# max_plate.net
KiCad netlist of a schematic drawn in EAGLE
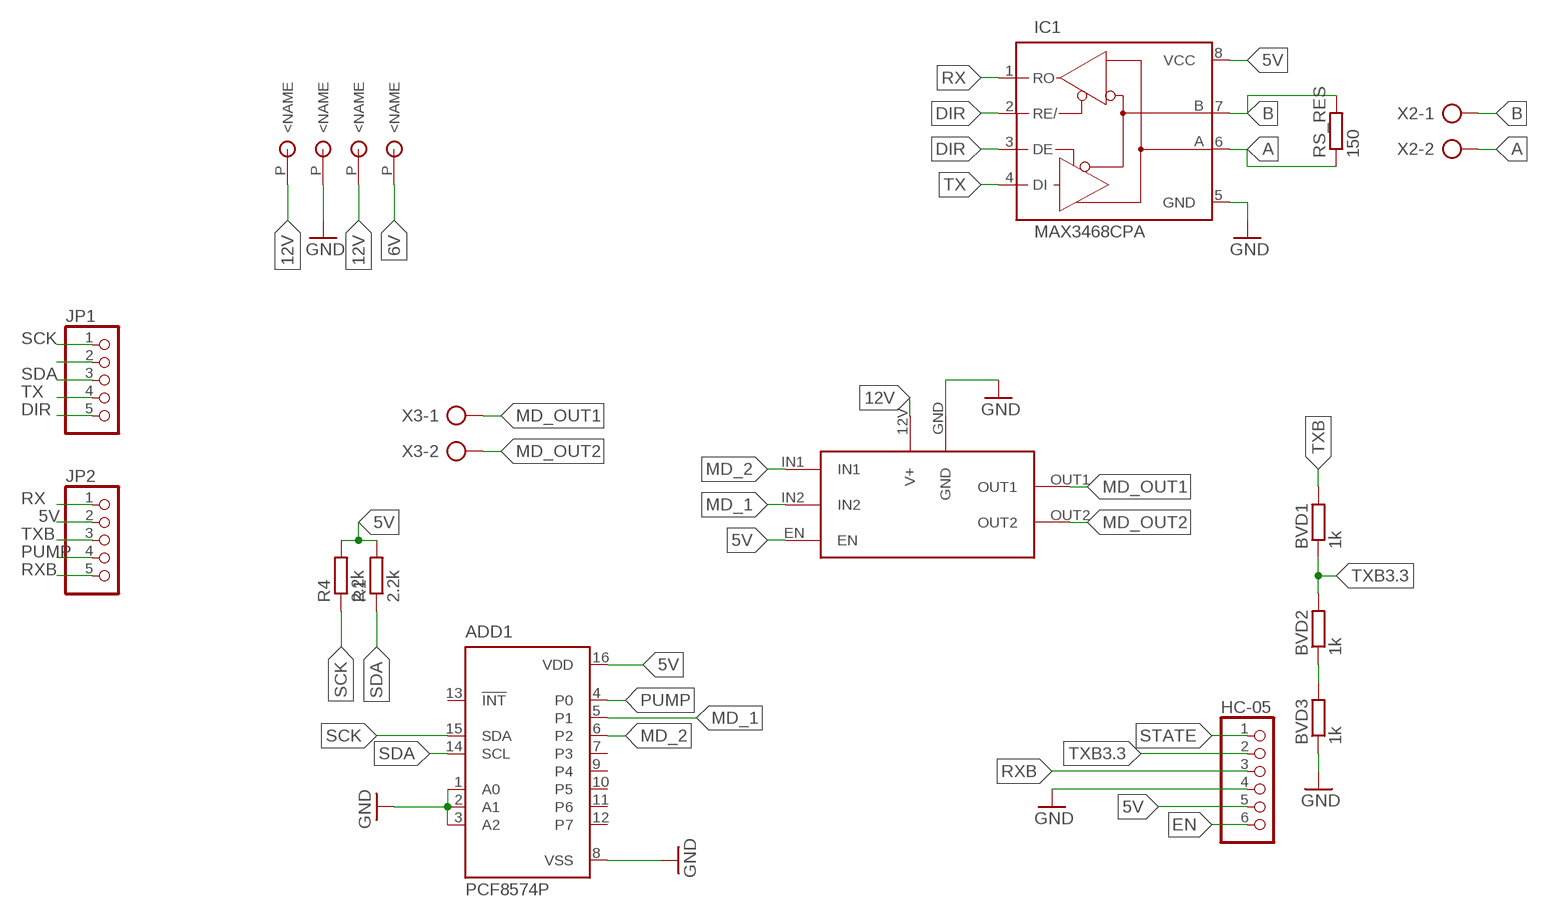
[diagram p0: schematic, sheet 1]

(export (version "E")
  (design (tool "Eeschema 10.0.6"))
  (components
    (comp (ref "ADD1")
      (value "PCF8574P")
      (footprint "eagle-import:DIL16")
      (fields (field (name "MPN") "PCF8574PN"))
      (libsource (lib "eagle-import") (part "PCF8574P"))
    )
    (comp (ref "BVD1")
      (value "1k")
      (footprint "eagle-import:0207_10")
      (libsource (lib "eagle-import") (part "R-EU_0207/10"))
    )
    (comp (ref "BVD2")
      (value "1k")
      (footprint "eagle-import:0207_10")
      (libsource (lib "eagle-import") (part "R-EU_0207/10"))
    )
    (comp (ref "BVD3")
      (value "1k")
      (footprint "eagle-import:0207_10")
      (libsource (lib "eagle-import") (part "R-EU_0207/10"))
    )
    (comp (ref "HC-05")
      (value "PINHD-1X6")
      (footprint "eagle-import:1X06")
      (libsource (lib "eagle-import") (part "PINHD-1X6"))
    )
    (comp (ref "IC1")
      (value "MAX3468CPA")
      (footprint "eagle-import:DIL08")
      (libsource (lib "eagle-import") (part "MAX34PA68C"))
    )
    (comp (ref "JP1")
      (value "PINHD-1X5")
      (footprint "eagle-import:1X05")
      (libsource (lib "eagle-import") (part "PINHD-1X5"))
    )
    (comp (ref "JP2")
      (value "PINHD-1X5")
      (footprint "eagle-import:1X05")
      (libsource (lib "eagle-import") (part "PINHD-1X5"))
    )
    (comp (ref "R1")
      (value "2.2k")
      (footprint "eagle-import:0207_10")
      (libsource (lib "eagle-import") (part "R-EU_0207/10"))
    )
    (comp (ref "R4")
      (value "2.2k")
      (footprint "eagle-import:0207_10")
      (libsource (lib "eagle-import") (part "R-EU_0207/10"))
    )
    (comp (ref "RS_RES")
      (value "150")
      (footprint "eagle-import:0207_10")
      (libsource (lib "eagle-import") (part "R-EU_0207/10"))
    )
    (comp (ref "U$1")
      (value "CU-SPACER")
      (footprint "eagle-import:CU-SPACER")
      (libsource (lib "eagle-import") (part "CU-SPACER"))
    )
    (comp (ref "U$2")
      (value "CU-SPACER")
      (footprint "eagle-import:CU-SPACER")
      (libsource (lib "eagle-import") (part "CU-SPACER"))
    )
    (comp (ref "U$3")
      (value "CU-SPACER")
      (footprint "eagle-import:CU-SPACER")
      (libsource (lib "eagle-import") (part "CU-SPACER"))
    )
    (comp (ref "U$4")
      (value "CU-SPACER")
      (footprint "eagle-import:CU-SPACER")
      (libsource (lib "eagle-import") (part "CU-SPACER"))
    )
    (comp (ref "U$5")
      (value "L6203-MODULE")
      (footprint "eagle-import:L6203-MODULE")
      (libsource (lib "eagle-import") (part "L6203-MODULE"))
    )
    (comp (ref "X2")
      (value "AK500/2")
      (footprint "eagle-import:AK500_2")
      (libsource (lib "eagle-import") (part "AK500/2"))
    )
    (comp (ref "X3")
      (value "AK500/2")
      (footprint "eagle-import:AK500_2")
      (libsource (lib "eagle-import") (part "AK500/2"))
    )
  )
  (nets
    (net (code "1") (name "5V") (class "Default")
      (node (ref "ADD1") (pin "16") (pinfunction "VDD_16") (pintype "power_in"))
      (node (ref "HC-05") (pin "5") (pinfunction "5_5") (pintype "passive"))
      (node (ref "IC1") (pin "8") (pinfunction "VCC_8") (pintype "power_in"))
      (node (ref "JP2") (pin "2") (pinfunction "2_2") (pintype "passive"))
      (node (ref "R1") (pin "2") (pinfunction "2_2") (pintype "passive"))
      (node (ref "R4") (pin "2") (pinfunction "2_2") (pintype "passive"))
      (node (ref "U$5") (pin "EN") (pinfunction "EN_EN") (pintype "bidirectional"))
    )
    (net (code "2") (name "6V") (class "Default")
      (node (ref "U$4") (pin "P") (pinfunction "<NAME_P") (pintype "bidirectional"))
    )
    (net (code "3") (name "12V") (class "Default")
      (node (ref "U$1") (pin "P") (pinfunction "<NAME_P") (pintype "bidirectional"))
      (node (ref "U$3") (pin "P") (pinfunction "<NAME_P") (pintype "bidirectional"))
      (node (ref "U$5") (pin "12V") (pinfunction "V+_12V") (pintype "bidirectional"))
    )
    (net (code "4") (name "A") (class "Default")
      (node (ref "IC1") (pin "6") (pinfunction "A_6") (pintype "passive"))
      (node (ref "RS_RES") (pin "1") (pinfunction "1_1") (pintype "passive"))
      (node (ref "X2") (pin "2") (pinfunction "KL_2") (pintype "passive"))
    )
    (net (code "5") (name "B") (class "Default")
      (node (ref "IC1") (pin "7") (pinfunction "B_7") (pintype "passive"))
      (node (ref "RS_RES") (pin "2") (pinfunction "2_2") (pintype "passive"))
      (node (ref "X2") (pin "1") (pinfunction "KL_1") (pintype "passive"))
    )
    (net (code "6") (name "DIR") (class "Default")
      (node (ref "IC1") (pin "2") (pinfunction "RE/_2") (pintype "input"))
      (node (ref "IC1") (pin "3") (pinfunction "DE_3") (pintype "input"))
      (node (ref "JP1") (pin "5") (pinfunction "5_5") (pintype "passive"))
    )
    (net (code "7") (name "EN") (class "Default")
      (node (ref "HC-05") (pin "6") (pinfunction "6_6") (pintype "passive"))
    )
    (net (code "8") (name "GND") (class "Default")
      (node (ref "ADD1") (pin "1") (pinfunction "A0_1") (pintype "input"))
      (node (ref "ADD1") (pin "2") (pinfunction "A1_2") (pintype "input"))
      (node (ref "ADD1") (pin "3") (pinfunction "A2_3") (pintype "input"))
      (node (ref "ADD1") (pin "8") (pinfunction "VSS_8") (pintype "power_in"))
      (node (ref "BVD3") (pin "1") (pinfunction "1_1") (pintype "passive"))
      (node (ref "HC-05") (pin "4") (pinfunction "4_4") (pintype "passive"))
      (node (ref "IC1") (pin "5") (pinfunction "GND_5") (pintype "power_in"))
      (node (ref "U$2") (pin "P") (pinfunction "<NAME_P") (pintype "bidirectional"))
      (node (ref "U$5") (pin "GND") (pinfunction "GND_GND") (pintype "bidirectional"))
    )
    (net (code "9") (name "MD_1") (class "Default")
      (node (ref "ADD1") (pin "5") (pinfunction "P1_5") (pintype "bidirectional"))
      (node (ref "U$5") (pin "IN2") (pinfunction "IN2_IN2") (pintype "bidirectional"))
    )
    (net (code "10") (name "MD_2") (class "Default")
      (node (ref "ADD1") (pin "6") (pinfunction "P2_6") (pintype "bidirectional"))
      (node (ref "U$5") (pin "IN1") (pinfunction "IN1_IN1") (pintype "bidirectional"))
    )
    (net (code "11") (name "MD_OUT1") (class "Default")
      (node (ref "U$5") (pin "OUT1") (pinfunction "OUT1_OUT1") (pintype "bidirectional"))
      (node (ref "X3") (pin "1") (pinfunction "KL_1") (pintype "passive"))
    )
    (net (code "12") (name "MD_OUT2") (class "Default")
      (node (ref "U$5") (pin "OUT2") (pinfunction "OUT2_OUT2") (pintype "bidirectional"))
      (node (ref "X3") (pin "2") (pinfunction "KL_2") (pintype "passive"))
    )
    (net (code "13") (name "Net-(BVD2-Pad1)") (class "Default")
      (node (ref "BVD2") (pin "1") (pinfunction "1_1") (pintype "passive"))
      (node (ref "BVD3") (pin "2") (pinfunction "2_2") (pintype "passive"))
    )
    (net (code "14") (name "PUMP") (class "Default")
      (node (ref "ADD1") (pin "4") (pinfunction "P0_4") (pintype "bidirectional"))
      (node (ref "JP2") (pin "4") (pinfunction "4_4") (pintype "passive"))
    )
    (net (code "15") (name "RX") (class "Default")
      (node (ref "IC1") (pin "1") (pinfunction "RO_1") (pintype "output"))
      (node (ref "JP2") (pin "1") (pinfunction "1_1") (pintype "passive"))
    )
    (net (code "16") (name "RXB") (class "Default")
      (node (ref "HC-05") (pin "3") (pinfunction "3_3") (pintype "passive"))
      (node (ref "JP2") (pin "5") (pinfunction "5_5") (pintype "passive"))
    )
    (net (code "17") (name "SCK") (class "Default")
      (node (ref "ADD1") (pin "15") (pinfunction "SDA_15") (pintype "bidirectional"))
      (node (ref "JP1") (pin "1") (pinfunction "1_1") (pintype "passive"))
      (node (ref "R4") (pin "1") (pinfunction "1_1") (pintype "passive"))
    )
    (net (code "18") (name "SDA") (class "Default")
      (node (ref "ADD1") (pin "14") (pinfunction "SCL_14") (pintype "input"))
      (node (ref "JP1") (pin "3") (pinfunction "3_3") (pintype "passive"))
      (node (ref "R1") (pin "1") (pinfunction "1_1") (pintype "passive"))
    )
    (net (code "19") (name "STATE") (class "Default")
      (node (ref "HC-05") (pin "1") (pinfunction "1_1") (pintype "passive"))
    )
    (net (code "20") (name "TX") (class "Default")
      (node (ref "IC1") (pin "4") (pinfunction "DI_4") (pintype "input"))
      (node (ref "JP1") (pin "4") (pinfunction "4_4") (pintype "passive"))
    )
    (net (code "21") (name "TXB") (class "Default")
      (node (ref "BVD1") (pin "2") (pinfunction "2_2") (pintype "passive"))
      (node (ref "JP2") (pin "3") (pinfunction "3_3") (pintype "passive"))
    )
    (net (code "22") (name "TXB3.3") (class "Default")
      (node (ref "BVD1") (pin "1") (pinfunction "1_1") (pintype "passive"))
      (node (ref "BVD2") (pin "2") (pinfunction "2_2") (pintype "passive"))
      (node (ref "HC-05") (pin "2") (pinfunction "2_2") (pintype "passive"))
    )
    (net (code "23") (name "unconnected-(ADD1-P3-Pad7)") (class "Default")
      (node (ref "ADD1") (pin "7") (pinfunction "P3_7") (pintype "bidirectional"))
    )
    (net (code "24") (name "unconnected-(ADD1-P4-Pad9)") (class "Default")
      (node (ref "ADD1") (pin "9") (pinfunction "P4_9") (pintype "bidirectional"))
    )
    (net (code "25") (name "unconnected-(ADD1-P5-Pad10)") (class "Default")
      (node (ref "ADD1") (pin "10") (pinfunction "P5_10") (pintype "bidirectional"))
    )
    (net (code "26") (name "unconnected-(ADD1-P6-Pad11)") (class "Default")
      (node (ref "ADD1") (pin "11") (pinfunction "P6_11") (pintype "bidirectional"))
    )
    (net (code "27") (name "unconnected-(ADD1-P7-Pad12)") (class "Default")
      (node (ref "ADD1") (pin "12") (pinfunction "P7_12") (pintype "bidirectional"))
    )
    (net (code "28") (name "unconnected-(ADD1-~{INT}-Pad13)") (class "Default")
      (node (ref "ADD1") (pin "13") (pinfunction "~{INT}_13") (pintype "output"))
    )
    (net (code "29") (name "unconnected-(JP1-Pad2)") (class "Default")
      (node (ref "JP1") (pin "2") (pinfunction "2_2") (pintype "passive"))
    )
  )
)
